# 7697_motor_driver_board.net
KiCad netlist of a schematic drawn in EAGLE
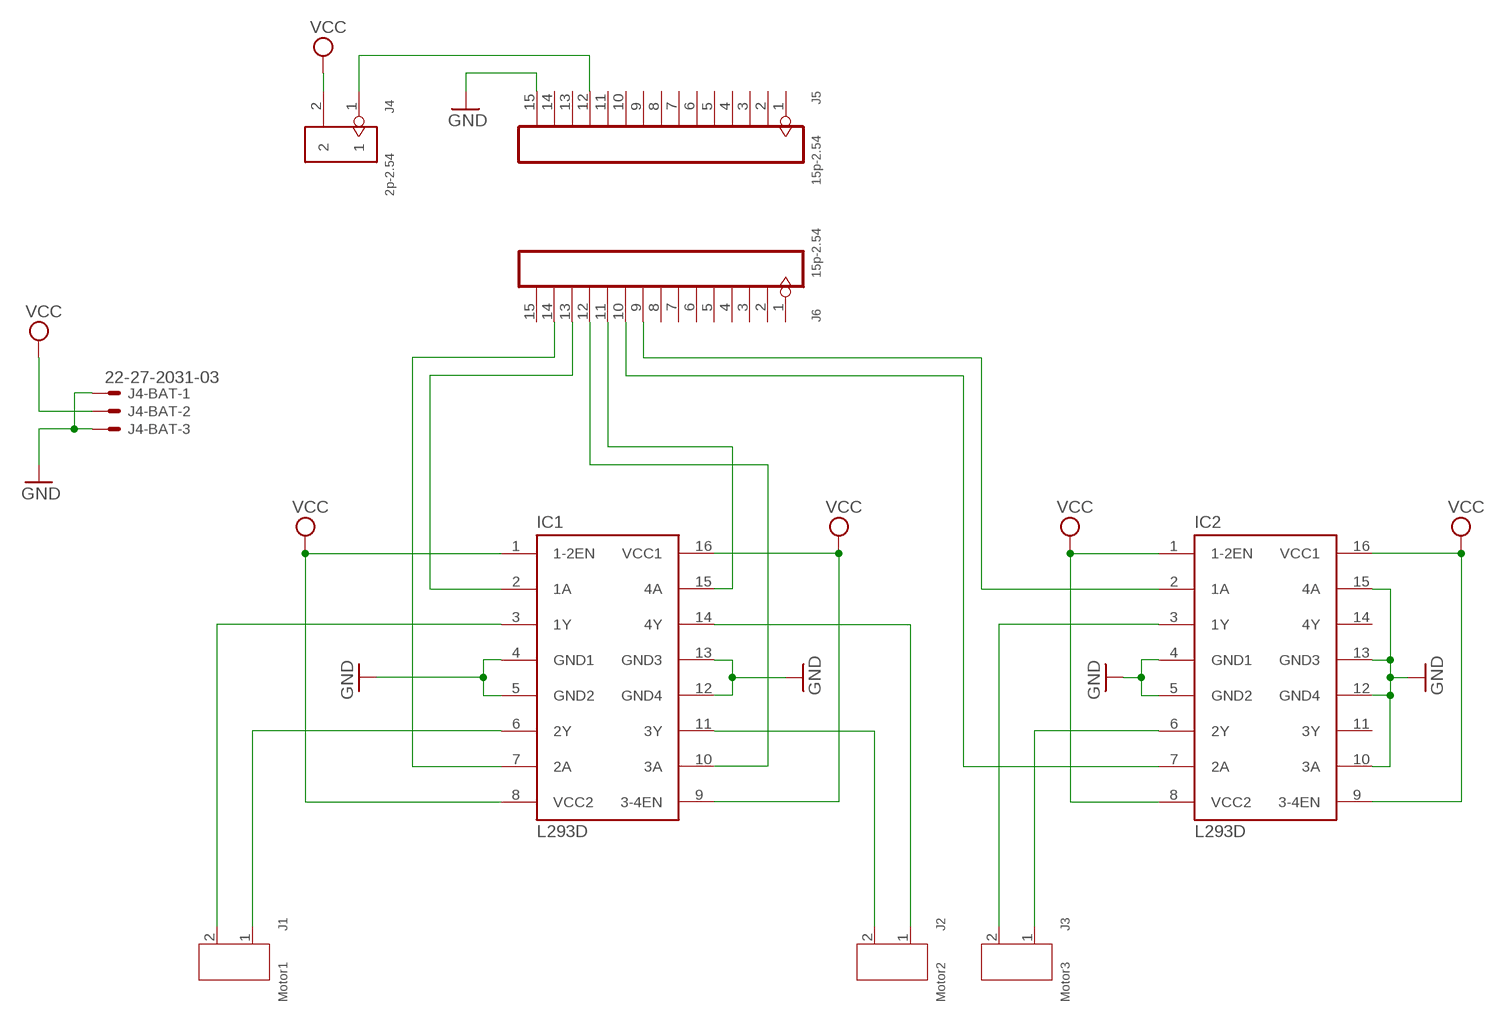
[diagram p0: schematic, sheet 1]

(export (version "E")
  (design (tool "Eeschema 10.0.6"))
  (components
    (comp (ref "IC1")
      (value "L293D")
      (footprint "eagle-import:DIL16")
      (libsource (lib "eagle-import") (part "L293D"))
    )
    (comp (ref "IC2")
      (value "L293D")
      (footprint "eagle-import:DIL16")
      (libsource (lib "eagle-import") (part "L293D"))
    )
    (comp (ref "J1")
      (value "Motor1")
      (footprint "eagle-import:H2-3.5-7.0X7.0MM")
      (libsource (lib "eagle-import") (part "SCREW-TERMINAL-GREEN(2P-3.5)"))
    )
    (comp (ref "J2")
      (value "Motor2")
      (footprint "eagle-import:H2-3.5-7.0X7.0MM")
      (libsource (lib "eagle-import") (part "SCREW-TERMINAL-GREEN(2P-3.5)"))
    )
    (comp (ref "J3")
      (value "Motor3")
      (footprint "eagle-import:H2-3.5-7.0X7.0MM")
      (libsource (lib "eagle-import") (part "SCREW-TERMINAL-GREEN(2P-3.5)"))
    )
    (comp (ref "J4")
      (value "2p-2.54")
      (footprint "eagle-import:H2-2.54")
      (fields (field (name "MPN") "P125-1102A0BS116A1"))
      (libsource (lib "eagle-import") (part "DIP-BLACK-MALE-HEADER-VERT(2P-2.54)"))
    )
    (comp (ref "J4-BAT")
      (value "22-27-2031-03")
      (footprint "eagle-import:6410-03")
      (libsource (lib "eagle-import") (part "22-?-0327-2031"))
    )
    (comp (ref "J5")
      (value "15p-2.54")
      (footprint "eagle-import:H15-2.54")
      (libsource (lib "eagle-import") (part "DIP-BLACK-FEMALE-HEADER-VERT(15P-2.54)"))
    )
    (comp (ref "J6")
      (value "15p-2.54")
      (footprint "eagle-import:H15-2.54")
      (libsource (lib "eagle-import") (part "DIP-BLACK-FEMALE-HEADER-VERT(15P-2.54)"))
    )
  )
  (nets
    (net (code "1") (name "GND") (class "Default")
      (node (ref "IC1") (pin "12") (pinfunction "GND4_12") (pintype "power_in"))
      (node (ref "IC1") (pin "13") (pinfunction "GND3_13") (pintype "power_in"))
      (node (ref "IC1") (pin "4") (pinfunction "GND1_4") (pintype "power_in"))
      (node (ref "IC1") (pin "5") (pinfunction "GND2_5") (pintype "power_in"))
      (node (ref "IC2") (pin "10") (pinfunction "3A_10") (pintype "input"))
      (node (ref "IC2") (pin "12") (pinfunction "GND4_12") (pintype "power_in"))
      (node (ref "IC2") (pin "13") (pinfunction "GND3_13") (pintype "power_in"))
      (node (ref "IC2") (pin "15") (pinfunction "4A_15") (pintype "input"))
      (node (ref "IC2") (pin "4") (pinfunction "GND1_4") (pintype "power_in"))
      (node (ref "IC2") (pin "5") (pinfunction "GND2_5") (pintype "power_in"))
      (node (ref "J4-BAT") (pin "1") (pinfunction "S_1") (pintype "passive"))
      (node (ref "J4-BAT") (pin "3") (pinfunction "S_3") (pintype "passive"))
      (node (ref "J5") (pin "15") (pinfunction "15_15") (pintype "passive"))
    )
    (net (code "2") (name "Net-(IC1-1A)") (class "Default")
      (node (ref "IC1") (pin "2") (pinfunction "1A_2") (pintype "input"))
      (node (ref "J6") (pin "13") (pinfunction "13_13") (pintype "passive"))
    )
    (net (code "3") (name "Net-(IC1-1Y)") (class "Default")
      (node (ref "IC1") (pin "3") (pinfunction "1Y_3") (pintype "output"))
      (node (ref "J1") (pin "2") (pinfunction "2_2") (pintype "bidirectional"))
    )
    (net (code "4") (name "Net-(IC1-2A)") (class "Default")
      (node (ref "IC1") (pin "7") (pinfunction "2A_7") (pintype "input"))
      (node (ref "J6") (pin "14") (pinfunction "14_14") (pintype "passive"))
    )
    (net (code "5") (name "Net-(IC1-2Y)") (class "Default")
      (node (ref "IC1") (pin "6") (pinfunction "2Y_6") (pintype "output"))
      (node (ref "J1") (pin "1") (pinfunction "1_1") (pintype "bidirectional"))
    )
    (net (code "6") (name "Net-(IC1-3A)") (class "Default")
      (node (ref "IC1") (pin "10") (pinfunction "3A_10") (pintype "input"))
      (node (ref "J6") (pin "12") (pinfunction "12_12") (pintype "passive"))
    )
    (net (code "7") (name "Net-(IC1-3Y)") (class "Default")
      (node (ref "IC1") (pin "11") (pinfunction "3Y_11") (pintype "output"))
      (node (ref "J2") (pin "2") (pinfunction "2_2") (pintype "bidirectional"))
    )
    (net (code "8") (name "Net-(IC1-4A)") (class "Default")
      (node (ref "IC1") (pin "15") (pinfunction "4A_15") (pintype "input"))
      (node (ref "J6") (pin "11") (pinfunction "11_11") (pintype "passive"))
    )
    (net (code "9") (name "Net-(IC1-4Y)") (class "Default")
      (node (ref "IC1") (pin "14") (pinfunction "4Y_14") (pintype "output"))
      (node (ref "J2") (pin "1") (pinfunction "1_1") (pintype "bidirectional"))
    )
    (net (code "10") (name "Net-(IC2-1A)") (class "Default")
      (node (ref "IC2") (pin "2") (pinfunction "1A_2") (pintype "input"))
      (node (ref "J6") (pin "9") (pinfunction "9_9") (pintype "passive"))
    )
    (net (code "11") (name "Net-(IC2-1Y)") (class "Default")
      (node (ref "IC2") (pin "3") (pinfunction "1Y_3") (pintype "output"))
      (node (ref "J3") (pin "2") (pinfunction "2_2") (pintype "bidirectional"))
    )
    (net (code "12") (name "Net-(IC2-2A)") (class "Default")
      (node (ref "IC2") (pin "7") (pinfunction "2A_7") (pintype "input"))
      (node (ref "J6") (pin "10") (pinfunction "10_10") (pintype "passive"))
    )
    (net (code "13") (name "Net-(IC2-2Y)") (class "Default")
      (node (ref "IC2") (pin "6") (pinfunction "2Y_6") (pintype "output"))
      (node (ref "J3") (pin "1") (pinfunction "1_1") (pintype "bidirectional"))
    )
    (net (code "14") (name "Net-(J4-Pad1)") (class "Default")
      (node (ref "J4") (pin "1") (pinfunction "1_1") (pintype "bidirectional"))
      (node (ref "J5") (pin "12") (pinfunction "12_12") (pintype "passive"))
    )
    (net (code "15") (name "VCC") (class "Default")
      (node (ref "IC1") (pin "1") (pinfunction "1-2EN_1") (pintype "input"))
      (node (ref "IC1") (pin "16") (pinfunction "VCC1_16") (pintype "power_in"))
      (node (ref "IC1") (pin "8") (pinfunction "VCC2_8") (pintype "power_in"))
      (node (ref "IC1") (pin "9") (pinfunction "3-4EN_9") (pintype "input"))
      (node (ref "IC2") (pin "1") (pinfunction "1-2EN_1") (pintype "input"))
      (node (ref "IC2") (pin "16") (pinfunction "VCC1_16") (pintype "power_in"))
      (node (ref "IC2") (pin "8") (pinfunction "VCC2_8") (pintype "power_in"))
      (node (ref "IC2") (pin "9") (pinfunction "3-4EN_9") (pintype "input"))
      (node (ref "J4") (pin "2") (pinfunction "2_2") (pintype "bidirectional"))
      (node (ref "J4-BAT") (pin "2") (pinfunction "S_2") (pintype "passive"))
    )
    (net (code "16") (name "unconnected-(IC2-3Y-Pad11)") (class "Default")
      (node (ref "IC2") (pin "11") (pinfunction "3Y_11") (pintype "output"))
    )
    (net (code "17") (name "unconnected-(IC2-4Y-Pad14)") (class "Default")
      (node (ref "IC2") (pin "14") (pinfunction "4Y_14") (pintype "output"))
    )
    (net (code "18") (name "unconnected-(J5-Pad1)") (class "Default")
      (node (ref "J5") (pin "1") (pinfunction "1_1") (pintype "passive"))
    )
    (net (code "19") (name "unconnected-(J5-Pad2)") (class "Default")
      (node (ref "J5") (pin "2") (pinfunction "2_2") (pintype "passive"))
    )
    (net (code "20") (name "unconnected-(J5-Pad3)") (class "Default")
      (node (ref "J5") (pin "3") (pinfunction "3_3") (pintype "passive"))
    )
    (net (code "21") (name "unconnected-(J5-Pad4)") (class "Default")
      (node (ref "J5") (pin "4") (pinfunction "4_4") (pintype "passive"))
    )
    (net (code "22") (name "unconnected-(J5-Pad5)") (class "Default")
      (node (ref "J5") (pin "5") (pinfunction "5_5") (pintype "passive"))
    )
    (net (code "23") (name "unconnected-(J5-Pad6)") (class "Default")
      (node (ref "J5") (pin "6") (pinfunction "6_6") (pintype "passive"))
    )
    (net (code "24") (name "unconnected-(J5-Pad7)") (class "Default")
      (node (ref "J5") (pin "7") (pinfunction "7_7") (pintype "passive"))
    )
    (net (code "25") (name "unconnected-(J5-Pad8)") (class "Default")
      (node (ref "J5") (pin "8") (pinfunction "8_8") (pintype "passive"))
    )
    (net (code "26") (name "unconnected-(J5-Pad9)") (class "Default")
      (node (ref "J5") (pin "9") (pinfunction "9_9") (pintype "passive"))
    )
    (net (code "27") (name "unconnected-(J5-Pad10)") (class "Default")
      (node (ref "J5") (pin "10") (pinfunction "10_10") (pintype "passive"))
    )
    (net (code "28") (name "unconnected-(J5-Pad11)") (class "Default")
      (node (ref "J5") (pin "11") (pinfunction "11_11") (pintype "passive"))
    )
    (net (code "29") (name "unconnected-(J5-Pad13)") (class "Default")
      (node (ref "J5") (pin "13") (pinfunction "13_13") (pintype "passive"))
    )
    (net (code "30") (name "unconnected-(J5-Pad14)") (class "Default")
      (node (ref "J5") (pin "14") (pinfunction "14_14") (pintype "passive"))
    )
    (net (code "31") (name "unconnected-(J6-Pad1)") (class "Default")
      (node (ref "J6") (pin "1") (pinfunction "1_1") (pintype "passive"))
    )
    (net (code "32") (name "unconnected-(J6-Pad2)") (class "Default")
      (node (ref "J6") (pin "2") (pinfunction "2_2") (pintype "passive"))
    )
    (net (code "33") (name "unconnected-(J6-Pad3)") (class "Default")
      (node (ref "J6") (pin "3") (pinfunction "3_3") (pintype "passive"))
    )
    (net (code "34") (name "unconnected-(J6-Pad4)") (class "Default")
      (node (ref "J6") (pin "4") (pinfunction "4_4") (pintype "passive"))
    )
    (net (code "35") (name "unconnected-(J6-Pad5)") (class "Default")
      (node (ref "J6") (pin "5") (pinfunction "5_5") (pintype "passive"))
    )
    (net (code "36") (name "unconnected-(J6-Pad6)") (class "Default")
      (node (ref "J6") (pin "6") (pinfunction "6_6") (pintype "passive"))
    )
    (net (code "37") (name "unconnected-(J6-Pad7)") (class "Default")
      (node (ref "J6") (pin "7") (pinfunction "7_7") (pintype "passive"))
    )
    (net (code "38") (name "unconnected-(J6-Pad8)") (class "Default")
      (node (ref "J6") (pin "8") (pinfunction "8_8") (pintype "passive"))
    )
    (net (code "39") (name "unconnected-(J6-Pad15)") (class "Default")
      (node (ref "J6") (pin "15") (pinfunction "15_15") (pintype "passive"))
    )
  )
)
